# r1.net
KiCad netlist of a schematic drawn in EasyEDA
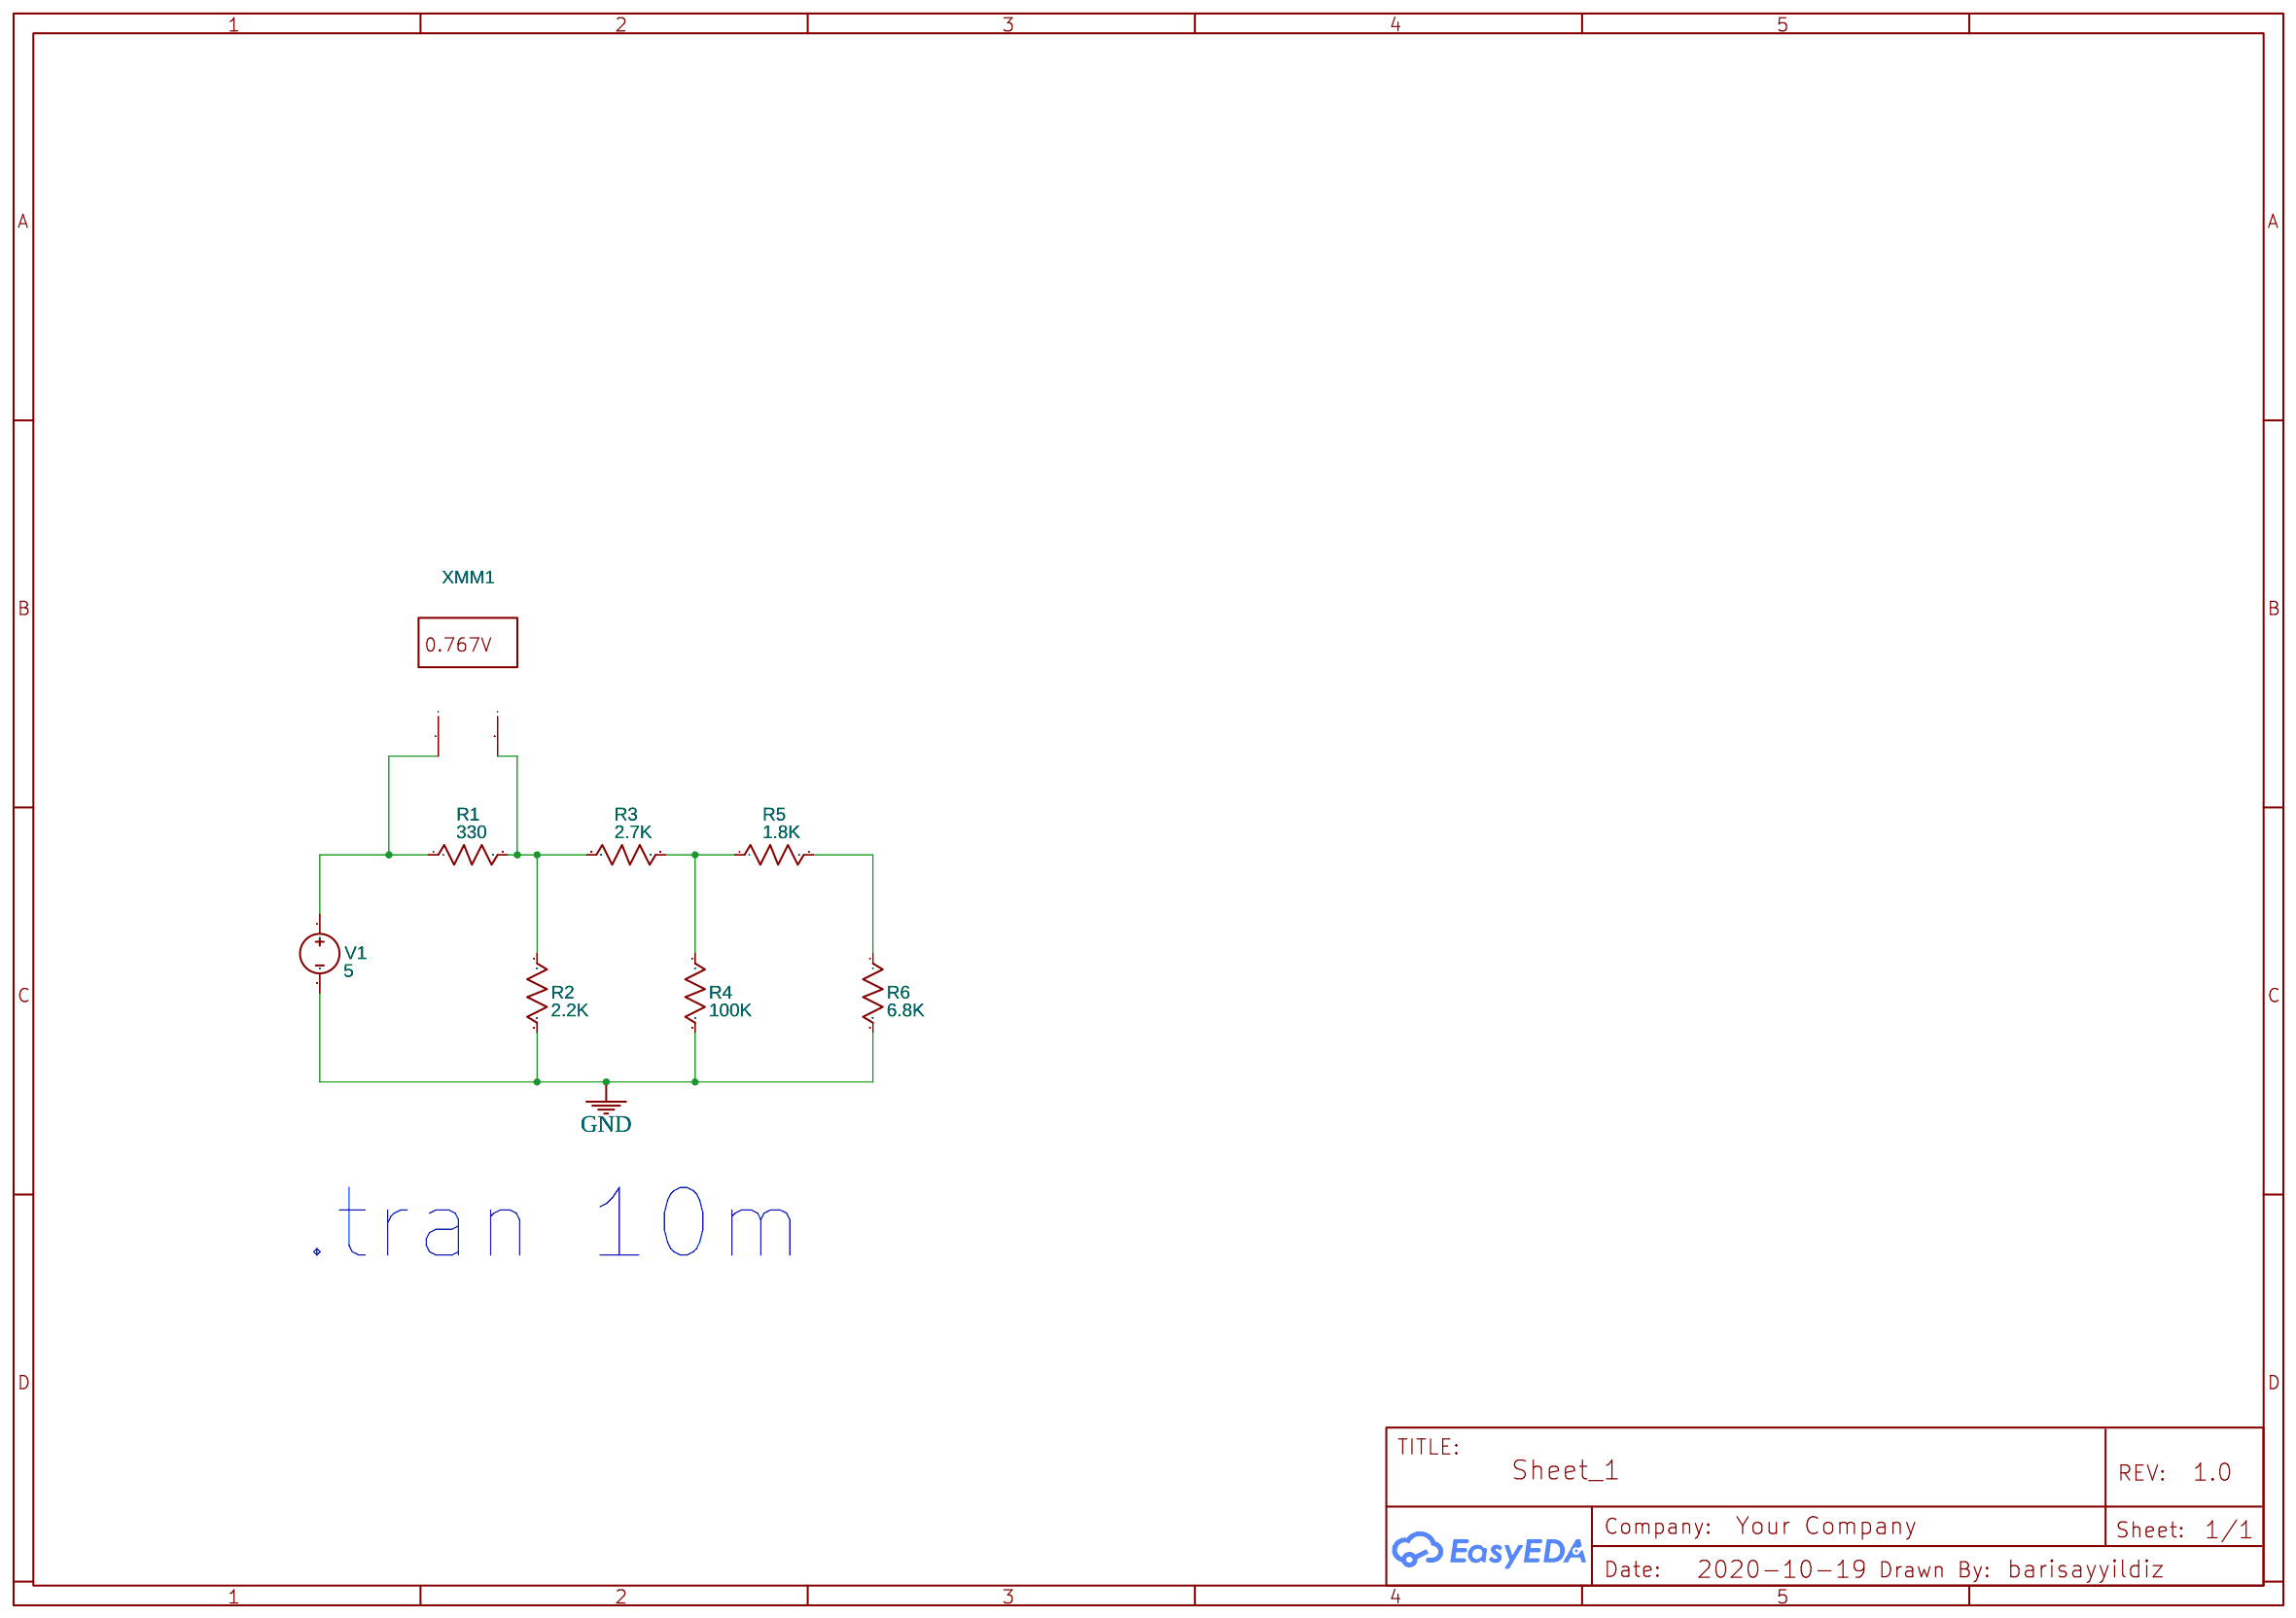
[diagram p0: schematic sheet]

(export (version "E")
  (design (tool "Eeschema 10.0.6"))
  (components
    (comp (ref "R1") (value "330") (libsource (lib "") (part "Resistor_US")))
    (comp (ref "R2") (value "2.2K") (libsource (lib "") (part "Resistor_US_1")))
    (comp (ref "R3") (value "2.7K") (libsource (lib "") (part "Resistor_US")))
    (comp (ref "R4") (value "100K") (libsource (lib "") (part "Resistor_US_1")))
    (comp (ref "R5") (value "1.8K") (libsource (lib "") (part "Resistor_US")))
    (comp (ref "R6") (value "6.8K") (libsource (lib "") (part "Resistor_US_1")))
    (comp (ref "V1") (value "5") (libsource (lib "") (part "VDC")))
    (comp (ref "XMM1") (value "Multimeter") (libsource (lib "") (part "MULTIMETER")))
  )
  (nets
    (net (code "1") (name "GND") (class "Default")
      (node (ref "R2") (pin "2") (pinfunction "2_2") (pintype "unspecified"))
      (node (ref "R4") (pin "2") (pinfunction "2_2") (pintype "unspecified"))
      (node (ref "R6") (pin "2") (pinfunction "2_2") (pintype "unspecified"))
      (node (ref "V1") (pin "2") (pinfunction "2_2") (pintype "unspecified"))
    )
    (net (code "2") (name "Net-(R3-Pad2)") (class "Default")
      (node (ref "R3") (pin "2") (pinfunction "2_2") (pintype "unspecified"))
      (node (ref "R4") (pin "1") (pinfunction "1_1") (pintype "unspecified"))
      (node (ref "R5") (pin "1") (pinfunction "1_1") (pintype "unspecified"))
    )
    (net (code "3") (name "Net-(R5-Pad2)") (class "Default")
      (node (ref "R5") (pin "2") (pinfunction "2_2") (pintype "unspecified"))
      (node (ref "R6") (pin "1") (pinfunction "1_1") (pintype "unspecified"))
    )
    (net (code "4") (name "Net-(XMM1-+)") (class "Default")
      (node (ref "R1") (pin "1") (pinfunction "1_1") (pintype "unspecified"))
      (node (ref "V1") (pin "1") (pinfunction "1_1") (pintype "unspecified"))
      (node (ref "XMM1") (pin "1") (pinfunction "+_1") (pintype "unspecified"))
    )
    (net (code "5") (name "Net-(XMM1-I)") (class "Default")
      (node (ref "R1") (pin "2") (pinfunction "2_2") (pintype "unspecified"))
      (node (ref "R2") (pin "1") (pinfunction "1_1") (pintype "unspecified"))
      (node (ref "R3") (pin "1") (pinfunction "1_1") (pintype "unspecified"))
      (node (ref "XMM1") (pin "2") (pinfunction "I_2") (pintype "unspecified"))
    )
  )
)
